# headstage-64-coax-adapter.net
KiCad netlist of a schematic drawn in EAGLE
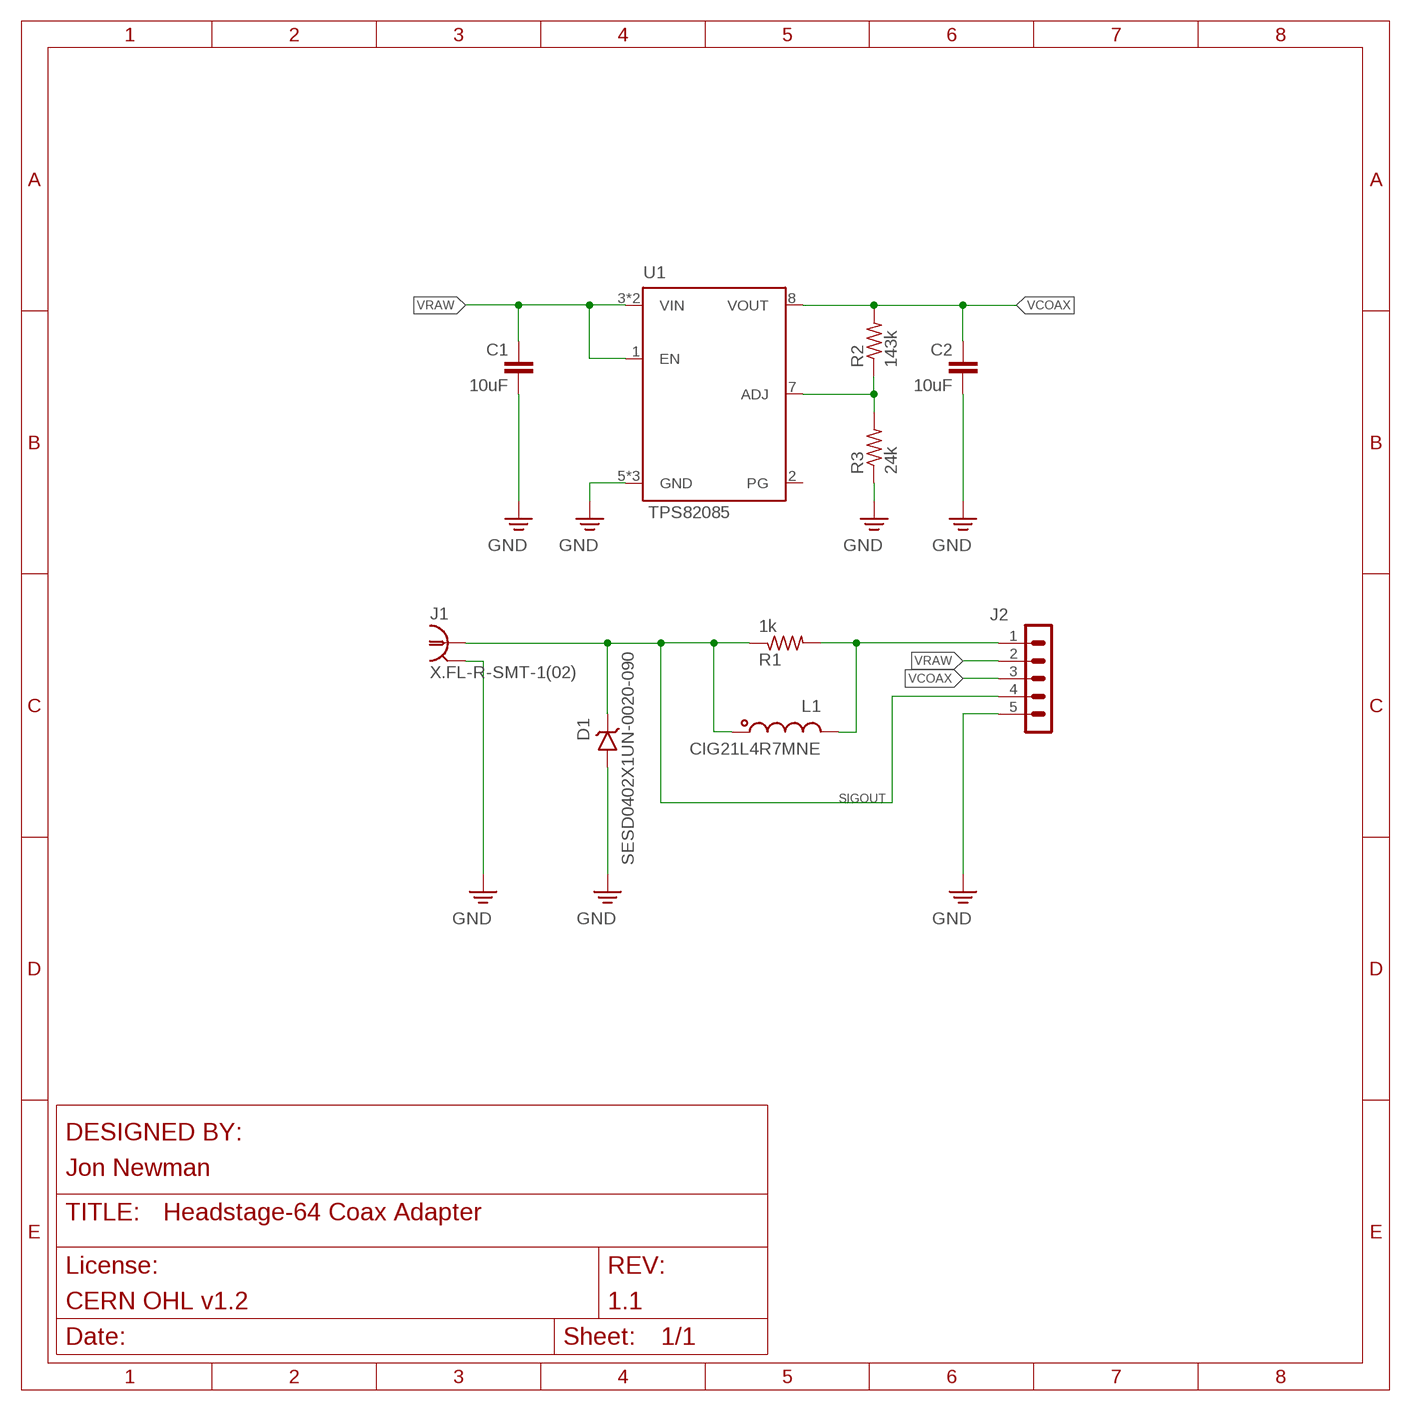
[diagram p0: schematic, sheet 1]

(export (version "E")
  (design (tool "Eeschema 10.0.6"))
  (components
    (comp (ref "C1")
      (value "10uF")
      (footprint "eagle-import:0402T")
      (fields (field (name "PARTNO") "CL05A475MO5NUNC"))
      (libsource (lib "eagle-import") (part "C_0402T"))
    )
    (comp (ref "C2")
      (value "10uF")
      (footprint "eagle-import:0402T")
      (fields (field (name "PARTNO") "CL05A475MO5NUNC"))
      (libsource (lib "eagle-import") (part "C_0402T"))
    )
    (comp (ref "D1")
      (value "SESD0402X1UN-0020-090")
      (footprint "eagle-import:0402T-DFN")
      (libsource (lib "eagle-import") (part "Z-DIODE_0402T-DFN"))
    )
    (comp (ref "J1")
      (value "X.FL-R-SMT-1(02)")
      (footprint "eagle-import:X_FL_R_SMT_1(02)")
      (libsource (lib "eagle-import") (part "COAX_XFL"))
    )
    (comp (ref "J2")
      (value "PINHD-1X5_HEADSTAGE-64-REV1.4-DAUGHTER-CARD-CASTELLATED")
      (footprint "eagle-import:HEADSTAGE-64-REV1.4-DAUGHTER-CARD-CASTELLATED")
      (libsource (lib "eagle-import") (part "PINHD-1X5_HEADSTAGE-64-REV1.4-DAUGHTER-CARD-CASTELLATED"))
    )
    (comp (ref "L1")
      (value "CIG21L4R7MNE")
      (footprint "eagle-import:0805T")
      (libsource (lib "eagle-import") (part "L_0805T"))
    )
    (comp (ref "R1")
      (value "1k")
      (footprint "eagle-import:0201T")
      (libsource (lib "eagle-import") (part "R_0201T"))
    )
    (comp (ref "R2")
      (value "143k")
      (footprint "eagle-import:0201T")
      (libsource (lib "eagle-import") (part "R_0201T"))
    )
    (comp (ref "R3")
      (value "24k")
      (footprint "eagle-import:0201T")
      (libsource (lib "eagle-import") (part "R_0201T"))
    )
    (comp (ref "U1")
      (value "TPS82085")
      (footprint "eagle-import:MICROSIP9-2.8X3")
      (libsource (lib "eagle-import") (part "TPS8208X"))
    )
  )
  (nets
    (net (code "1") (name "/SIGOUT") (class "Default")
      (node (ref "D1") (pin "C") (pinfunction "C_C") (pintype "passive"))
      (node (ref "J1") (pin "P$1") (pinfunction "1_P$1") (pintype "passive"))
      (node (ref "J2") (pin "4") (pinfunction "4_4") (pintype "passive"))
      (node (ref "L1") (pin "1") (pinfunction "1_1") (pintype "passive"))
      (node (ref "R1") (pin "1") (pinfunction "1_1") (pintype "passive"))
    )
    (net (code "2") (name "GND") (class "Default")
      (node (ref "C1") (pin "2") (pinfunction "2_2") (pintype "passive"))
      (node (ref "C2") (pin "2") (pinfunction "2_2") (pintype "passive"))
      (node (ref "D1") (pin "A") (pinfunction "A_A") (pintype "passive"))
      (node (ref "J1") (pin "P$2") (pinfunction "2_P$2") (pintype "passive"))
      (node (ref "J1") (pin "P$3") (pinfunction "2_P$3") (pintype "passive"))
      (node (ref "J1") (pin "P$4") (pinfunction "2_P$4") (pintype "passive"))
      (node (ref "J2") (pin "5") (pinfunction "5_5") (pintype "passive"))
      (node (ref "R3") (pin "1") (pinfunction "1_1") (pintype "passive"))
      (node (ref "U1") (pin "5") (pinfunction "GND_5") (pintype "power_in"))
      (node (ref "U1") (pin "6") (pinfunction "GND_6") (pintype "power_in"))
      (node (ref "U1") (pin "PAD") (pinfunction "GND_PAD") (pintype "power_in"))
    )
    (net (code "3") (name "Net-(J2-Pad1)") (class "Default")
      (node (ref "J2") (pin "1") (pinfunction "1_1") (pintype "passive"))
      (node (ref "L1") (pin "2") (pinfunction "2_2") (pintype "passive"))
      (node (ref "R1") (pin "2") (pinfunction "2_2") (pintype "passive"))
    )
    (net (code "4") (name "Net-(U1-ADJ)") (class "Default")
      (node (ref "R2") (pin "1") (pinfunction "1_1") (pintype "passive"))
      (node (ref "R3") (pin "2") (pinfunction "2_2") (pintype "passive"))
      (node (ref "U1") (pin "7") (pinfunction "ADJ_7") (pintype "input"))
    )
    (net (code "5") (name "VCOAX") (class "Default")
      (node (ref "C2") (pin "1") (pinfunction "1_1") (pintype "passive"))
      (node (ref "J2") (pin "3") (pinfunction "3_3") (pintype "passive"))
      (node (ref "R2") (pin "2") (pinfunction "2_2") (pintype "passive"))
      (node (ref "U1") (pin "8") (pinfunction "VOUT_8") (pintype "power_in"))
    )
    (net (code "6") (name "VRAW") (class "Default")
      (node (ref "C1") (pin "1") (pinfunction "1_1") (pintype "passive"))
      (node (ref "J2") (pin "2") (pinfunction "2_2") (pintype "passive"))
      (node (ref "U1") (pin "1") (pinfunction "EN_1") (pintype "input"))
      (node (ref "U1") (pin "3") (pinfunction "VIN_3") (pintype "power_in"))
      (node (ref "U1") (pin "4") (pinfunction "VIN_4") (pintype "power_in"))
    )
    (net (code "7") (name "unconnected-(U1-PG-Pad2)") (class "Default")
      (node (ref "U1") (pin "2") (pinfunction "PG_2") (pintype "open_collector"))
    )
  )
)
